# COMPONENT_BLOCKS_2.net
KiCad netlist of a schematic drawn in Altium Designer
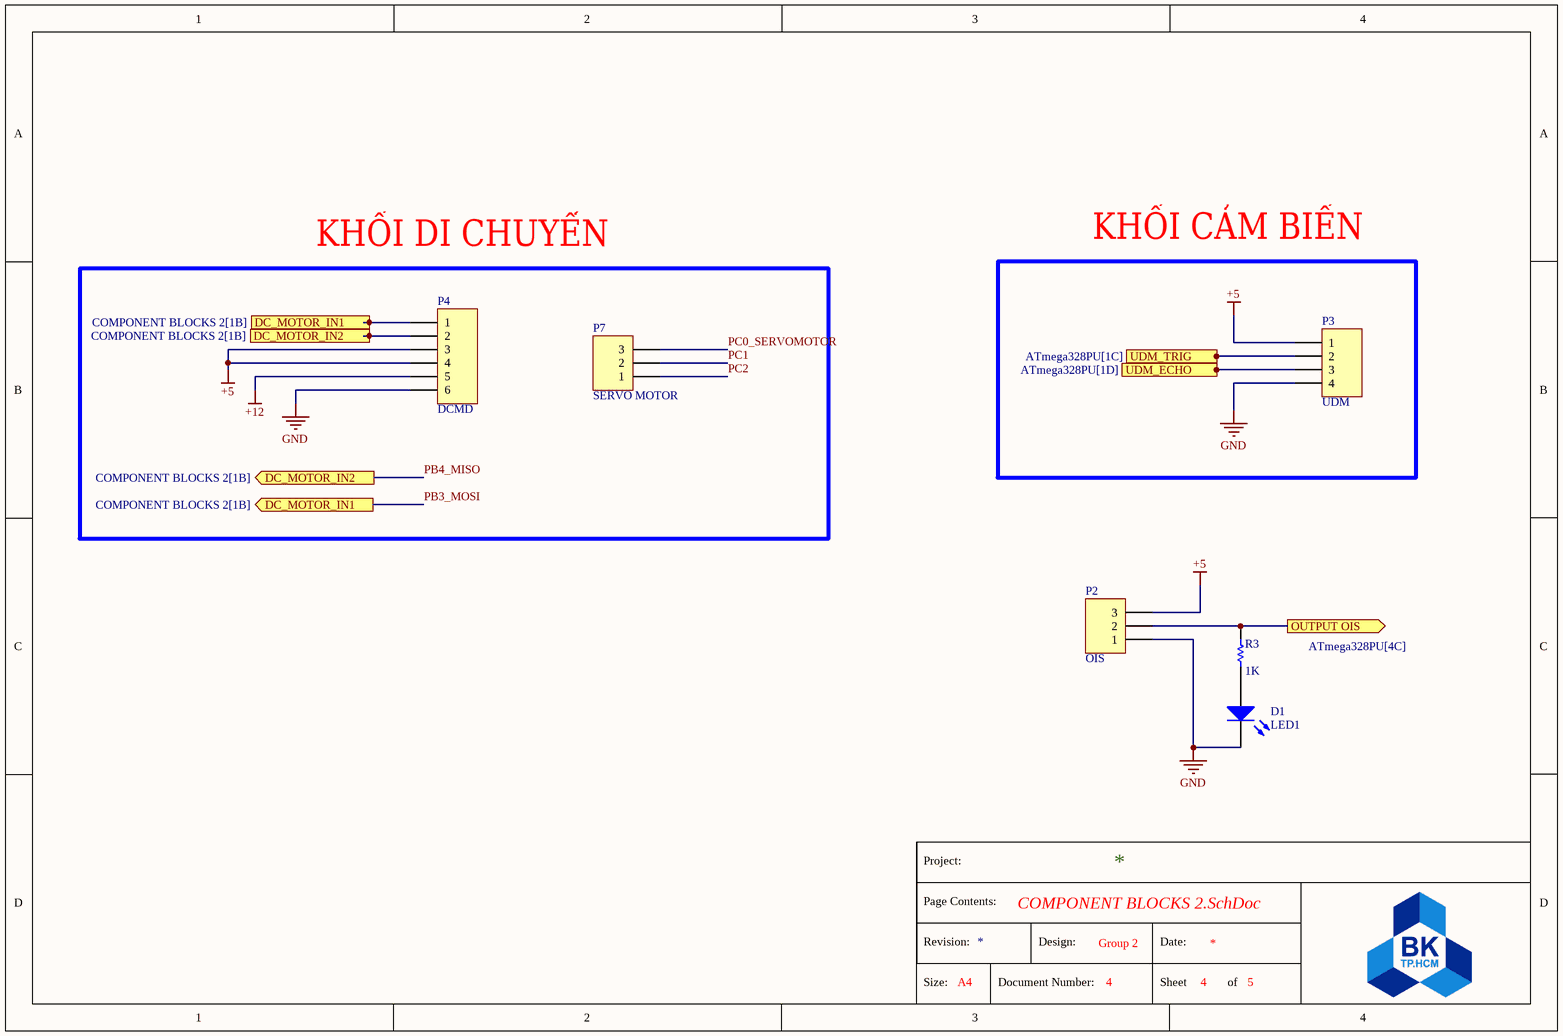
[diagram p0: COMPONENT BLOCKS 2.SchDoc]

(export (version "E")
  (design (tool "Eeschema 10.0.6"))
  (components
    (comp (ref "D1")
      (value "LED1")
      (footprint "LED-1")
      (description "Typical RED GaAs LED")
      (fields (field (name "PUBLISHER") "Altium Limited"))
      (libsource (lib "Miscellaneous Devices") (part "LED1"))
    )
    (comp (ref "P2")
      (value "OIS")
      (footprint "HDR1X3")
      (description "Header, 3-Pin")
      (fields (field (name "PUBLISHER") "Altium Limited"))
      (libsource (lib "Miscellaneous Connectors") (part "Header 3"))
    )
    (comp (ref "P3")
      (value "UDM")
      (footprint "HDR1X4")
      (description "Header, 4-Pin")
      (fields (field (name "PUBLISHER") "Altium Limited"))
      (libsource (lib "Miscellaneous Connectors") (part "Header 4"))
    )
    (comp (ref "P4")
      (value "DCMD")
      (footprint "HDR1X6")
      (description "Header, 6-Pin")
      (fields (field (name "PUBLISHER") "Altium Limited"))
      (libsource (lib "Miscellaneous Connectors") (part "Header 6"))
    )
    (comp (ref "P7")
      (value "SERVO MOTOR")
      (footprint "HDR1X3")
      (description "Header, 3-Pin")
      (fields (field (name "PUBLISHER") "Altium Limited"))
      (libsource (lib "Miscellaneous Connectors") (part "Header 3"))
    )
    (comp (ref "R3")
      (value "1K")
      (footprint "AXIAL-0.3")
      (description "Resistor")
      (fields (field (name "Comment") "Res1") (field (name "PUBLISHER") "Altium Limited"))
      (libsource (lib "Miscellaneous Devices") (part "Res1"))
    )
  )
  (nets
    (net (code "1") (name "+5") (class "Default")
      (node (ref "P2") (pin "3") (pinfunction "3_3") (pintype "passive"))
      (node (ref "P3") (pin "1") (pinfunction "1_1") (pintype "passive"))
      (node (ref "P4") (pin "3") (pinfunction "3_3") (pintype "passive"))
      (node (ref "P4") (pin "4") (pinfunction "4_4") (pintype "passive"))
    )
    (net (code "2") (name "+12") (class "Default")
      (node (ref "P4") (pin "5") (pinfunction "5_5") (pintype "passive"))
    )
    (net (code "3") (name "/OUTPUT OIS") (class "Default")
      (node (ref "P2") (pin "2") (pinfunction "2_2") (pintype "passive"))
      (node (ref "R3") (pin "2") (pinfunction "2_2") (pintype "passive"))
    )
    (net (code "4") (name "/PB3_MOSI") (class "Default")
      (node (ref "P4") (pin "1") (pinfunction "1_1") (pintype "passive"))
    )
    (net (code "5") (name "/PB4_MISO") (class "Default")
      (node (ref "P4") (pin "2") (pinfunction "2_2") (pintype "passive"))
    )
    (net (code "6") (name "/PC0_SERVOMOTOR") (class "Default")
      (node (ref "P7") (pin "3") (pinfunction "3_3") (pintype "passive"))
    )
    (net (code "7") (name "/PC1") (class "Default")
      (node (ref "P7") (pin "2") (pinfunction "2_2") (pintype "passive"))
    )
    (net (code "8") (name "/PC2") (class "Default")
      (node (ref "P7") (pin "1") (pinfunction "1_1") (pintype "passive"))
    )
    (net (code "9") (name "/UDM_ECHO") (class "Default")
      (node (ref "P3") (pin "3") (pinfunction "3_3") (pintype "passive"))
    )
    (net (code "10") (name "/UDM_TRIG") (class "Default")
      (node (ref "P3") (pin "2") (pinfunction "2_2") (pintype "passive"))
    )
    (net (code "11") (name "GND") (class "Default")
      (node (ref "D1") (pin "2") (pinfunction "K_2") (pintype "passive"))
      (node (ref "P2") (pin "1") (pinfunction "1_1") (pintype "passive"))
      (node (ref "P3") (pin "4") (pinfunction "4_4") (pintype "passive"))
      (node (ref "P4") (pin "6") (pinfunction "6_6") (pintype "passive"))
    )
    (net (code "12") (name "Net-(D1-A)") (class "Default")
      (node (ref "D1") (pin "1") (pinfunction "A_1") (pintype "passive"))
      (node (ref "R3") (pin "1") (pinfunction "1_1") (pintype "passive"))
    )
  )
)
